# piggyback.net
KiCad netlist of a schematic drawn in EAGLE
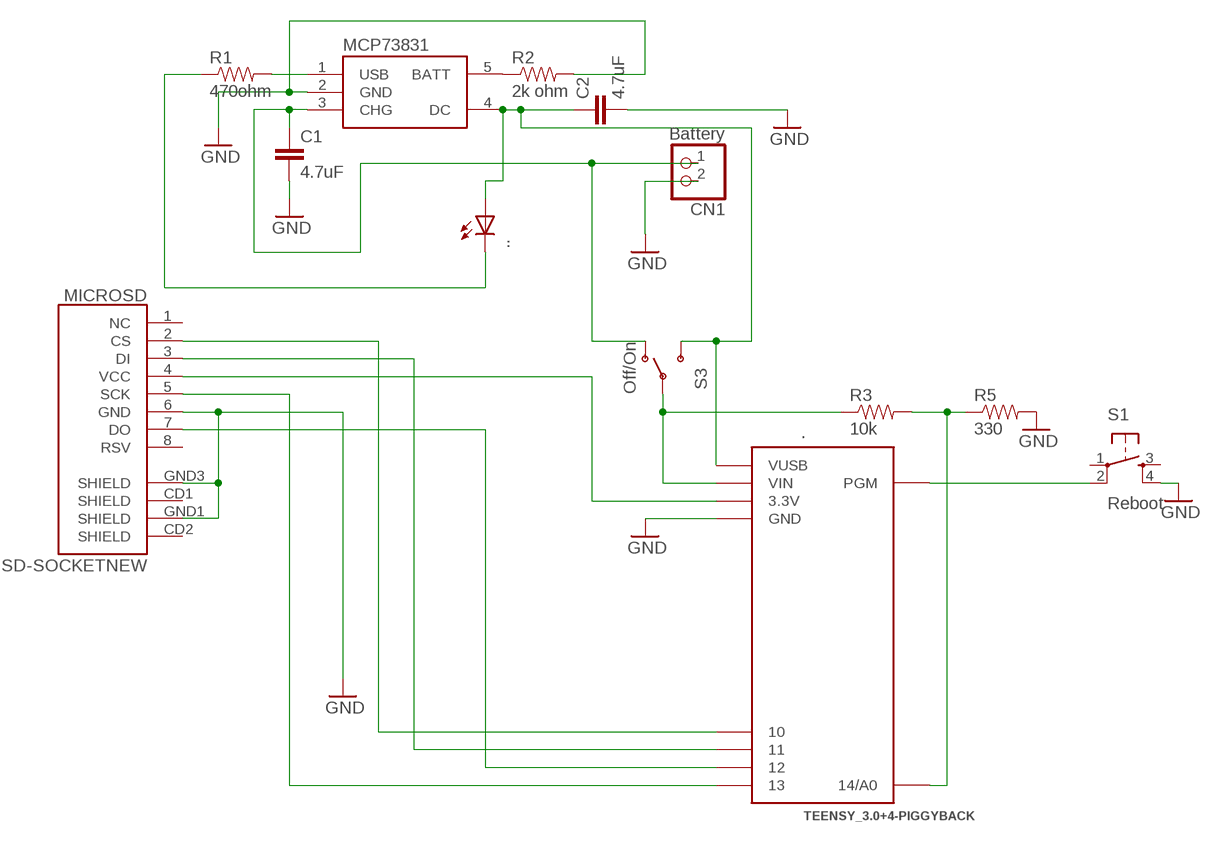
[diagram p0: schematic, sheet 1]

(export (version "E")
  (design (tool "Eeschema 10.0.6"))
  (components
    (comp (ref ".")
      (value "TEENSY_3.0+4-PIGGYBACK")
      (footprint "eagle-import:TEENSY_3.0+4-PIGGYBACK")
      (libsource (lib "eagle-import") (part "TEENSY_3.0+4-PIGGYBACK"))
    )
    (comp (ref "..")
      (value "LEDCHIP-LED0805")
      (footprint "eagle-import:CHIP-LED0805")
      (libsource (lib "eagle-import") (part "LEDCHIP-LED0805"))
    )
    (comp (ref "C1")
      (value "4.7uF")
      (footprint "eagle-import:0805")
      (libsource (lib "eagle-import") (part "CAP0805"))
    )
    (comp (ref "C2")
      (value "4.7uF")
      (footprint "eagle-import:0805")
      (libsource (lib "eagle-import") (part "CAP0805"))
    )
    (comp (ref "CN1")
      (value "Battery")
      (footprint "eagle-import:JST-PH-2-THM")
      (libsource (lib "eagle-import") (part "JST_2PIN-THM"))
    )
    (comp (ref "MCP73831")
      (value "MAX1555")
      (footprint "eagle-import:SOT23-5")
      (libsource (lib "eagle-import") (part "MAX1555"))
    )
    (comp (ref "MICROSD")
      (value "USD-SOCKETNEW")
      (footprint "eagle-import:MICRO-SD-SOCKET-PP")
      (libsource (lib "eagle-import") (part "USD-SOCKETNEW"))
    )
    (comp (ref "R1")
      (value "470ohm")
      (footprint "eagle-import:0805")
      (libsource (lib "eagle-import") (part "RESISTOR"))
    )
    (comp (ref "R2")
      (value "2k ohm")
      (footprint "eagle-import:0805")
      (libsource (lib "eagle-import") (part "RESISTOR"))
    )
    (comp (ref "R3")
      (value "10k")
      (footprint "eagle-import:0805")
      (libsource (lib "eagle-import") (part "RESISTOR0805-RES"))
    )
    (comp (ref "R5")
      (value "330")
      (footprint "eagle-import:0805")
      (libsource (lib "eagle-import") (part "RESISTOR0805-RES"))
    )
    (comp (ref "S1")
      (value "Reboot")
      (footprint "eagle-import:TACTILE_SWITCH_SMD")
      (libsource (lib "eagle-import") (part "TAC_SWITCHSMD"))
    )
    (comp (ref "S3")
      (value "Off/On")
      (footprint "eagle-import:SWITCH-SPST-SMD-A")
      (libsource (lib "eagle-import") (part "SWITCH-SPDT-SMD-A"))
    )
  )
  (nets
    (net (code "1") (name "GND") (class "Default")
      (node (ref ".") (pin "GND1") (pinfunction "GND_GND1") (pintype "power_in"))
      (node (ref "C1") (pin "2") (pinfunction "2_2") (pintype "passive"))
      (node (ref "C2") (pin "2") (pinfunction "2_2") (pintype "passive"))
      (node (ref "CN1") (pin "2") (pinfunction "1_2") (pintype "passive"))
      (node (ref "MCP73831") (pin "2") (pinfunction "GND_2") (pintype "bidirectional"))
      (node (ref "MICROSD") (pin "6") (pinfunction "GND_6") (pintype "bidirectional"))
      (node (ref "MICROSD") (pin "GND1") (pinfunction "SHIELD_GND1") (pintype "bidirectional"))
      (node (ref "MICROSD") (pin "GND3") (pinfunction "SHIELD_GND3") (pintype "bidirectional"))
      (node (ref "R2") (pin "2") (pinfunction "2_2") (pintype "passive"))
      (node (ref "R5") (pin "2") (pinfunction "2_2") (pintype "passive"))
      (node (ref "S1") (pin "4") (pinfunction "4_4") (pintype "passive"))
    )
    (net (code "2") (name "Net-(.-3.3V)") (class "Default")
      (node (ref ".") (pin "3.3V1") (pinfunction "3.3V_3.3V1") (pintype "power_in"))
      (node (ref "MICROSD") (pin "4") (pinfunction "VCC_4") (pintype "bidirectional"))
    )
    (net (code "3") (name "Net-(.-Pad14{slash}A0)") (class "Default")
      (node (ref ".") (pin "14/A0") (pinfunction "14/A0_14/A0") (pintype "bidirectional"))
      (node (ref "R3") (pin "2") (pinfunction "2_2") (pintype "passive"))
      (node (ref "R5") (pin "1") (pinfunction "1_1") (pintype "passive"))
    )
    (net (code "4") (name "Net-(.-PadPGM)") (class "Default")
      (node (ref ".") (pin "PGM") (pinfunction "PGM_PGM") (pintype "bidirectional"))
      (node (ref "S1") (pin "2") (pinfunction "2_2") (pintype "passive"))
    )
    (net (code "5") (name "Net-(..-PadC)") (class "Default")
      (node (ref "..") (pin "C") (pinfunction "C_C") (pintype "passive"))
      (node (ref "R1") (pin "1") (pinfunction "1_1") (pintype "passive"))
    )
    (net (code "6") (name "Net-(CN1-2)") (class "Default")
      (node (ref "C1") (pin "1") (pinfunction "1_1") (pintype "passive"))
      (node (ref "CN1") (pin "1") (pinfunction "2_1") (pintype "passive"))
      (node (ref "MCP73831") (pin "3") (pinfunction "CHG_3") (pintype "bidirectional"))
      (node (ref "S3") (pin "1") (pinfunction "O_1") (pintype "passive"))
    )
    (net (code "7") (name "Net-(MCP73831-BATT)") (class "Default")
      (node (ref "MCP73831") (pin "5") (pinfunction "BATT_5") (pintype "bidirectional"))
      (node (ref "R2") (pin "1") (pinfunction "1_1") (pintype "passive"))
    )
    (net (code "8") (name "Net-(MCP73831-DC)") (class "Default")
      (node (ref ".") (pin "VUSB") (pinfunction "VUSB_VUSB") (pintype "power_in"))
      (node (ref "..") (pin "A") (pinfunction "A_A") (pintype "passive"))
      (node (ref "C2") (pin "1") (pinfunction "1_1") (pintype "passive"))
      (node (ref "MCP73831") (pin "4") (pinfunction "DC_4") (pintype "bidirectional"))
      (node (ref "S3") (pin "3") (pinfunction "S_3") (pintype "passive"))
    )
    (net (code "9") (name "Net-(MCP73831-USB)") (class "Default")
      (node (ref "MCP73831") (pin "1") (pinfunction "USB_1") (pintype "bidirectional"))
      (node (ref "R1") (pin "2") (pinfunction "2_2") (pintype "passive"))
    )
    (net (code "10") (name "Net-(MICROSD-CS)") (class "Default")
      (node (ref ".") (pin "10") (pinfunction "10_10") (pintype "bidirectional"))
      (node (ref "MICROSD") (pin "2") (pinfunction "CS_2") (pintype "bidirectional"))
    )
    (net (code "11") (name "Net-(MICROSD-DI)") (class "Default")
      (node (ref ".") (pin "11") (pinfunction "11_11") (pintype "bidirectional"))
      (node (ref "MICROSD") (pin "3") (pinfunction "DI_3") (pintype "bidirectional"))
    )
    (net (code "12") (name "Net-(MICROSD-DO)") (class "Default")
      (node (ref ".") (pin "12") (pinfunction "12_12") (pintype "bidirectional"))
      (node (ref "MICROSD") (pin "7") (pinfunction "DO_7") (pintype "bidirectional"))
    )
    (net (code "13") (name "Net-(MICROSD-SCK)") (class "Default")
      (node (ref ".") (pin "13") (pinfunction "13_13") (pintype "bidirectional"))
      (node (ref "MICROSD") (pin "5") (pinfunction "SCK_5") (pintype "bidirectional"))
    )
    (net (code "14") (name "Net-(S3-P)") (class "Default")
      (node (ref ".") (pin "VIN") (pinfunction "VIN_VIN") (pintype "power_in"))
      (node (ref "R3") (pin "1") (pinfunction "1_1") (pintype "passive"))
      (node (ref "S3") (pin "2") (pinfunction "P_2") (pintype "passive"))
    )
    (net (code "15") (name "unconnected-(MICROSD-NC-Pad1)") (class "Default")
      (node (ref "MICROSD") (pin "1") (pinfunction "NC_1") (pintype "bidirectional"))
    )
    (net (code "16") (name "unconnected-(MICROSD-RSV-Pad8)") (class "Default")
      (node (ref "MICROSD") (pin "8") (pinfunction "RSV_8") (pintype "bidirectional"))
    )
    (net (code "17") (name "unconnected-(MICROSD-SHIELD-PadCD1)") (class "Default")
      (node (ref "MICROSD") (pin "CD1") (pinfunction "SHIELD_CD1") (pintype "bidirectional"))
    )
    (net (code "18") (name "unconnected-(MICROSD-SHIELD-PadCD2)") (class "Default")
      (node (ref "MICROSD") (pin "CD2") (pinfunction "SHIELD_CD2") (pintype "bidirectional"))
    )
    (net (code "19") (name "unconnected-(S1-Pad1)") (class "Default")
      (node (ref "S1") (pin "1") (pinfunction "1_1") (pintype "passive"))
    )
    (net (code "20") (name "unconnected-(S1-Pad3)") (class "Default")
      (node (ref "S1") (pin "3") (pinfunction "3_3") (pintype "passive"))
    )
  )
)
